# crystal_oscillator_low_freq.net
KiCad netlist of a schematic drawn in Altium Designer
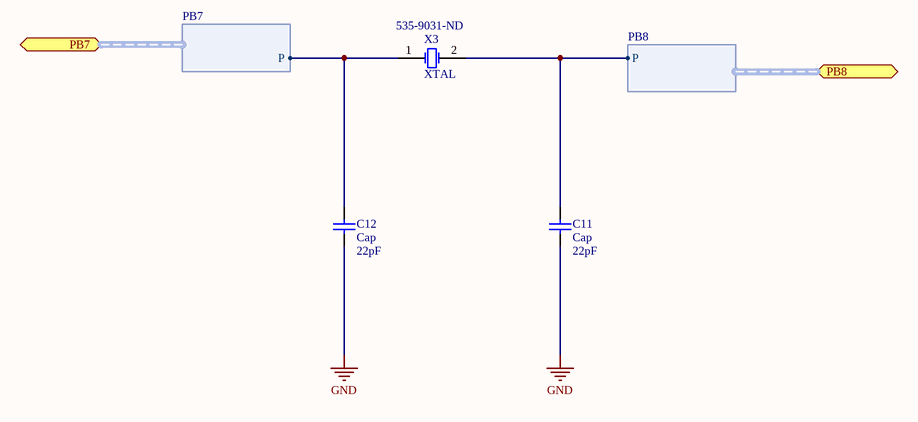
[diagram p0: crystal_oscillator_low_freq.SchDoc]

(export (version "E")
  (design (tool "Eeschema 10.0.6"))
  (components
    (comp (ref "C11")
      (value "Cap")
      (footprint "RAD-0.3")
      (description "Capacitor")
      (fields (field (name "ALTIUM_VALUE") "22pF") (field (name "PUBLISHER") "Altium Limited"))
      (libsource (lib "Miscellaneous Devices") (part "Cap"))
    )
    (comp (ref "C12")
      (value "Cap")
      (footprint "RAD-0.3")
      (description "Capacitor")
      (fields (field (name "ALTIUM_VALUE") "22pF") (field (name "PUBLISHER") "Altium Limited"))
      (libsource (lib "Miscellaneous Devices") (part "Cap"))
    )
    (comp (ref "X3")
      (value "XTAL")
      (footprint "R38")
      (description "Crystal Oscillator")
      (fields
        (field (name "SUPPLIER PART NUMBER 1") "535-9031-ND")
        (field (name "MANUFACTURER") "Abracon Corporation")
        (field (name "MANUFACTURER PART NUMBER") "AB15T-32.768KHZ")
        (field (name "PUBLISHER") "Altium Limited")
      )
      (libsource (lib "Miscellaneous Devices") (part "XTAL"))
    )
  )
  (nets
    (net (code "5") (name "GND") (class "Default")
      (node (ref "C11") (pin "1") (pinfunction "1_1") (pintype "passive"))
      (node (ref "C12") (pin "1") (pinfunction "1_1") (pintype "passive"))
    )
    (net (code "6") (name "Net-(X3-OSC1)") (class "Default")
      (node (ref "C12") (pin "2") (pinfunction "2_2") (pintype "passive"))
      (node (ref "X3") (pin "1") (pinfunction "OSC1_1") (pintype "passive"))
    )
    (net (code "7") (name "Net-(X3-OSC2)") (class "Default")
      (node (ref "C11") (pin "2") (pinfunction "2_2") (pintype "passive"))
      (node (ref "X3") (pin "2") (pinfunction "OSC2_2") (pintype "passive"))
    )
  )
)
